# Communication.net
KiCad netlist of a schematic drawn in Altium Designer
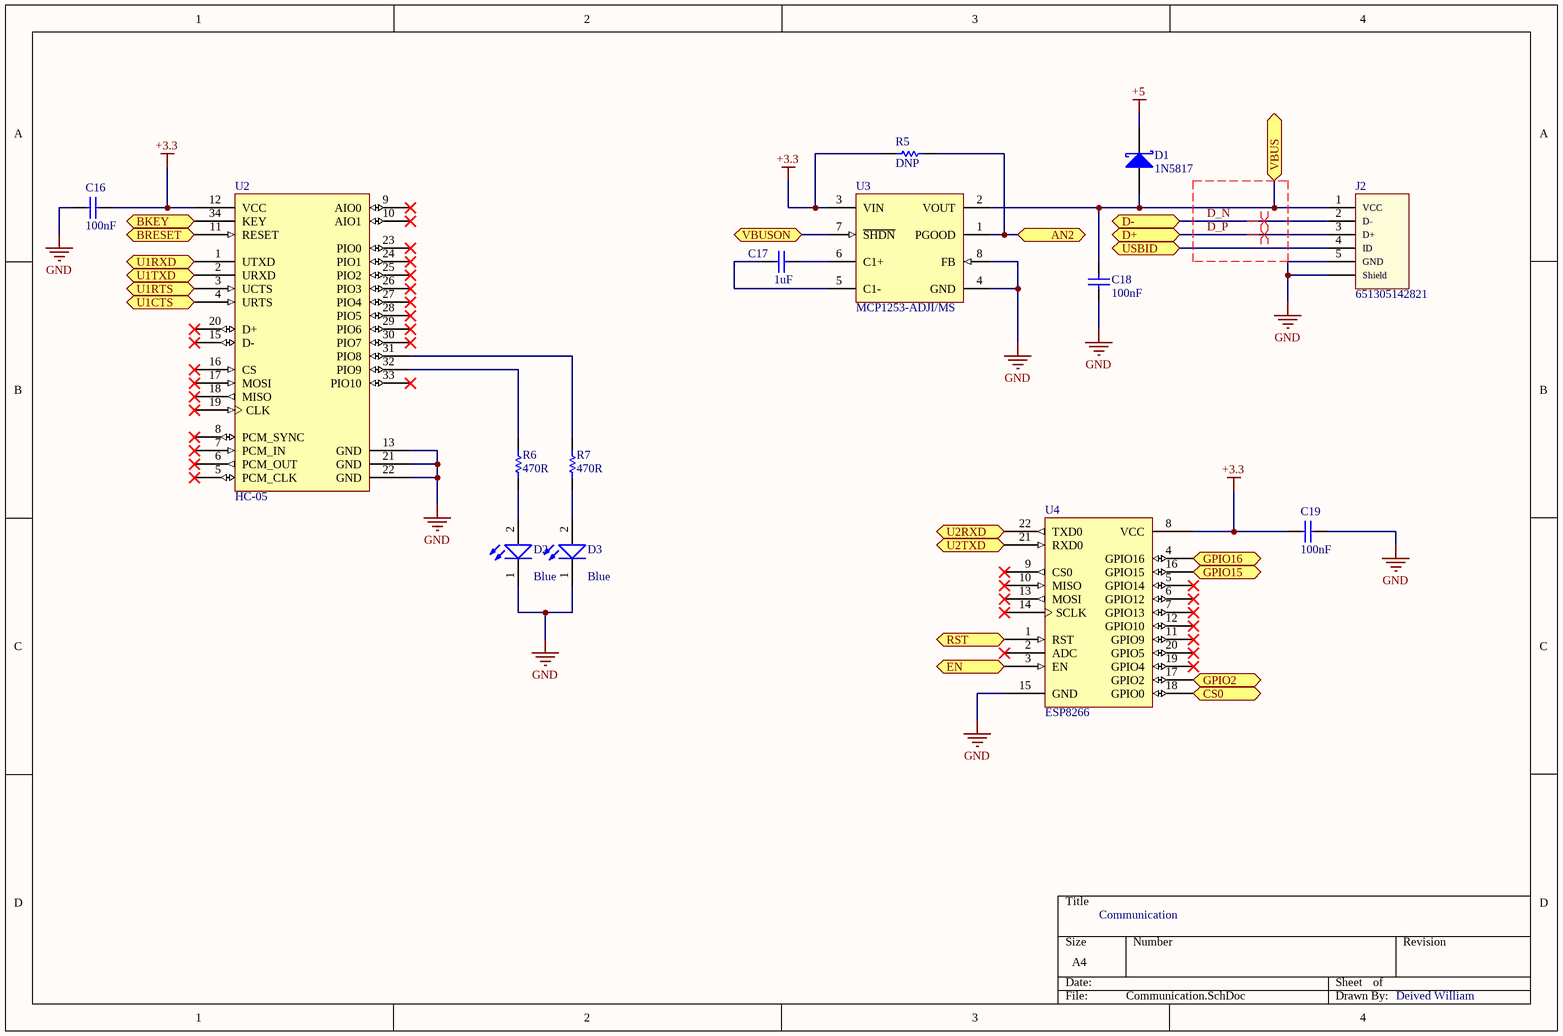
[diagram p0: Communication.SchDoc]

(export (version "E")
  (design (tool "Eeschema 10.0.6"))
  (components
    (comp (ref "C16")
      (value "100nF")
      (footprint "WCAP-CSGP_0603, 1.6x0.8x0.8mm_Reflow")
      (description "WCAP-CSGP Ceramic Capacitors, size 0603, 1.6x0.8x0.8mm, 10V, X7R, 100nF")
      (fields (field (name "PART NUMBER") "885012206020") (field (name "PUBLISHER") "Wurth Elektronik"))
      (libsource (lib "Altium_WCAP-CSGP (rev17a)") (part "885012206020"))
    )
    (comp (ref "C17")
      (value "1uF")
      (footprint "WCAP-CSGP_0603, 1.6x0.8x0.8mm_Reflow")
      (description "WCAP-CSGP Ceramic Capacitors, size 0603, 1.6x0.8x0.8mm, 25V, X5R, 1uF")
      (fields (field (name "PART NUMBER") "885012106022") (field (name "PUBLISHER") "Wurth Elektronik"))
      (libsource (lib "Altium_WCAP-CSGP (rev17a)") (part "885012106022"))
    )
    (comp (ref "C18")
      (value "100nF")
      (footprint "WCAP-CSGP_0603, 1.6x0.8x0.8mm_Reflow")
      (description "WCAP-CSGP Ceramic Capacitors, size 0603, 1.6x0.8x0.8mm, 10V, X7R, 100nF")
      (fields (field (name "PART NUMBER") "885012206020") (field (name "PUBLISHER") "Wurth Elektronik"))
      (libsource (lib "Altium_WCAP-CSGP (rev17a)") (part "885012206020"))
    )
    (comp (ref "C19")
      (value "100nF")
      (footprint "WCAP-CSGP_0603, 1.6x0.8x0.8mm_Reflow")
      (description "WCAP-CSGP Ceramic Capacitors, size 0603, 1.6x0.8x0.8mm, 10V, X7R, 100nF")
      (fields (field (name "PART NUMBER") "885012206020") (field (name "PUBLISHER") "Wurth Elektronik"))
      (libsource (lib "Altium_WCAP-CSGP (rev17a)") (part "885012206020"))
    )
    (comp (ref "D1")
      (value "1N5817")
      (footprint "MELFDIODE")
      (description "Schottky diode Barrier Rectifier")
      (libsource (lib "Componentes Deived Projetos") (part "1N5817"))
    )
    (comp (ref "D2")
      (value "150080BS75000")
      (footprint "WL-SMCW_0805")
      (description "WL-SMCW SMD Mono-color Chip LED Waterclear, size 0805, Blue")
      (fields (field (name "EMITTING COLOR") "Blue") (field (name "PUBLISHER") "Wurth Elektronik"))
      (libsource (lib "ALTIUM-WL-SMCW-rev17a") (part "150080BS75000"))
    )
    (comp (ref "D3")
      (value "150080BS75000")
      (footprint "WL-SMCW_0805")
      (description "WL-SMCW SMD Mono-color Chip LED Waterclear, size 0805, Blue")
      (fields (field (name "EMITTING COLOR") "Blue") (field (name "PUBLISHER") "Wurth Elektronik"))
      (libsource (lib "ALTIUM-WL-SMCW-rev17a") (part "150080BS75000"))
    )
    (comp (ref "J2")
      (value "651305142821")
      (footprint "651305142821")
      (description "Mini USB 2.0 Type AB SMT Horizontal 5 Contacts WR-COM")
      (fields (field (name "PUBLISHER") "Wurth Elektronik"))
      (libsource (lib "Altium_WR-COM (rev17a)") (part "651305142821"))
    )
    (comp (ref "R5")
      (value "DNP")
      (footprint "3-0603")
      (fields (field (name "PUBLISHER") "Altium Limited"))
      (libsource (lib "Panasonic Resistor") (part "ERJ3RB"))
    )
    (comp (ref "R6")
      (value "470R")
      (footprint "3-0603")
      (fields (field (name "PUBLISHER") "Altium Limited"))
      (libsource (lib "Panasonic Resistor") (part "ERJ3RE"))
    )
    (comp (ref "R7")
      (value "470R")
      (footprint "3-0603")
      (fields (field (name "PUBLISHER") "Altium Limited"))
      (libsource (lib "Panasonic Resistor") (part "ERJ3RE"))
    )
    (comp (ref "U2")
      (value "HC-05")
      (footprint "LCC42")
      (description "Modulo Bluetooth HC-05")
      (libsource (lib "Componentes Deived Projetos") (part "Bluetooth HC-05"))
    )
    (comp (ref "U3")
      (value "MCP1253-ADJI/MS")
      (footprint "MSOP-MS8_N")
      (fields (field (name "PUBLISHER") "Altium Limited"))
      (libsource (lib "Microchip Power Mgt Charge Pump") (part "MCP1253-ADJI/MS"))
    )
    (comp (ref "U4")
      (value "ESP8266")
      (footprint "LCC28")
      (description "Modulo WIFI ESP8266")
      (libsource (lib "Componentes Deived Projetos") (part "ESP8266"))
    )
  )
  (nets
    (net (code "1") (name "+3.3") (class "Default")
      (node (ref "C16") (pin "2") (pinfunction "2_2") (pintype "passive"))
      (node (ref "C19") (pin "1") (pinfunction "1_1") (pintype "passive"))
      (node (ref "R5") (pin "1") (pinfunction "1_1") (pintype "passive"))
      (node (ref "U2") (pin "12") (pinfunction "VCC_12") (pintype "power_in"))
      (node (ref "U3") (pin "3") (pinfunction "VIN_3") (pintype "power_in"))
      (node (ref "U4") (pin "8") (pinfunction "VCC_8") (pintype "passive"))
    )
    (net (code "2") (name "+5") (class "Default")
      (node (ref "D1") (pin "2") (pinfunction "K_2") (pintype "passive"))
    )
    (net (code "3") (name "/AN2") (class "Default")
      (node (ref "R5") (pin "2") (pinfunction "2_2") (pintype "passive"))
      (node (ref "U3") (pin "1") (pinfunction "PGOOD_1") (pintype "open_collector"))
    )
    (net (code "4") (name "/BKEY") (class "Default")
      (node (ref "U2") (pin "34") (pinfunction "KEY_34") (pintype "passive"))
    )
    (net (code "5") (name "/BRESET") (class "Default")
      (node (ref "U2") (pin "11") (pinfunction "RESET_11") (pintype "input"))
    )
    (net (code "6") (name "/CS0") (class "Default")
      (node (ref "U4") (pin "18") (pinfunction "GPIO0_18") (pintype "bidirectional"))
    )
    (net (code "7") (name "/D_N") (class "Default")
      (node (ref "J2") (pin "2") (pinfunction "D-_2") (pintype "passive"))
    )
    (net (code "8") (name "/D_P") (class "Default")
      (node (ref "J2") (pin "3") (pinfunction "D+_3") (pintype "passive"))
    )
    (net (code "9") (name "/EN") (class "Default")
      (node (ref "U4") (pin "3") (pinfunction "EN_3") (pintype "input"))
    )
    (net (code "10") (name "/GPIO2") (class "Default")
      (node (ref "U4") (pin "17") (pinfunction "GPIO2_17") (pintype "bidirectional"))
    )
    (net (code "11") (name "/GPIO15") (class "Default")
      (node (ref "U4") (pin "16") (pinfunction "GPIO15_16") (pintype "bidirectional"))
    )
    (net (code "12") (name "/GPIO16") (class "Default")
      (node (ref "U4") (pin "4") (pinfunction "GPIO16_4") (pintype "bidirectional"))
    )
    (net (code "13") (name "/RST") (class "Default")
      (node (ref "U4") (pin "1") (pinfunction "RST_1") (pintype "input"))
    )
    (net (code "14") (name "/U1CTS") (class "Default")
      (node (ref "U2") (pin "4") (pinfunction "URTS_4") (pintype "input"))
    )
    (net (code "15") (name "/U1RTS") (class "Default")
      (node (ref "U2") (pin "3") (pinfunction "UCTS_3") (pintype "input"))
    )
    (net (code "16") (name "/U1RXD") (class "Default")
      (node (ref "U2") (pin "1") (pinfunction "UTXD_1") (pintype "passive"))
    )
    (net (code "17") (name "/U1TXD") (class "Default")
      (node (ref "U2") (pin "2") (pinfunction "URXD_2") (pintype "passive"))
    )
    (net (code "18") (name "/U2RXD") (class "Default")
      (node (ref "U4") (pin "22") (pinfunction "TXD0_22") (pintype "output"))
    )
    (net (code "19") (name "/U2TXD") (class "Default")
      (node (ref "U4") (pin "21") (pinfunction "RXD0_21") (pintype "input"))
    )
    (net (code "20") (name "/USBID") (class "Default")
      (node (ref "J2") (pin "4") (pinfunction "ID_4") (pintype "passive"))
    )
    (net (code "21") (name "/VBUS") (class "Default")
      (node (ref "C18") (pin "2") (pinfunction "2_2") (pintype "passive"))
      (node (ref "D1") (pin "1") (pinfunction "A_1") (pintype "passive"))
      (node (ref "J2") (pin "1") (pinfunction "VCC_1") (pintype "passive"))
      (node (ref "U3") (pin "2") (pinfunction "VOUT_2") (pintype "power_in"))
    )
    (net (code "22") (name "/VBUSON") (class "Default")
      (node (ref "U3") (pin "7") (pinfunction "~{SHDN}_7") (pintype "input"))
    )
    (net (code "23") (name "GND") (class "Default")
      (node (ref "C16") (pin "1") (pinfunction "1_1") (pintype "passive"))
      (node (ref "C18") (pin "1") (pinfunction "1_1") (pintype "passive"))
      (node (ref "C19") (pin "2") (pinfunction "2_2") (pintype "passive"))
      (node (ref "D2") (pin "1") (pinfunction "K_1") (pintype "passive"))
      (node (ref "D3") (pin "1") (pinfunction "K_1") (pintype "passive"))
      (node (ref "J2") (pin "5") (pinfunction "GND_5") (pintype "passive"))
      (node (ref "J2") (pin "Shell") (pinfunction "Shield_Shell") (pintype "passive"))
      (node (ref "U2") (pin "13") (pinfunction "GND_13") (pintype "passive"))
      (node (ref "U2") (pin "21") (pinfunction "GND_21") (pintype "passive"))
      (node (ref "U2") (pin "22") (pinfunction "GND_22") (pintype "passive"))
      (node (ref "U3") (pin "4") (pinfunction "GND_4") (pintype "power_in"))
      (node (ref "U3") (pin "8") (pinfunction "FB_8") (pintype "input"))
      (node (ref "U4") (pin "15") (pinfunction "GND_15") (pintype "passive"))
    )
    (net (code "24") (name "Net-(D2-A)") (class "Default")
      (node (ref "D2") (pin "2") (pinfunction "A_2") (pintype "passive"))
      (node (ref "R6") (pin "1") (pinfunction "1_1") (pintype "passive"))
    )
    (net (code "25") (name "Net-(D3-A)") (class "Default")
      (node (ref "D3") (pin "2") (pinfunction "A_2") (pintype "passive"))
      (node (ref "R7") (pin "1") (pinfunction "1_1") (pintype "passive"))
    )
    (net (code "26") (name "Net-(U2-PIO8)") (class "Default")
      (node (ref "R7") (pin "2") (pinfunction "2_2") (pintype "passive"))
      (node (ref "U2") (pin "31") (pinfunction "PIO8_31") (pintype "bidirectional"))
    )
    (net (code "27") (name "Net-(U2-PIO9)") (class "Default")
      (node (ref "R6") (pin "2") (pinfunction "2_2") (pintype "passive"))
      (node (ref "U2") (pin "32") (pinfunction "PIO9_32") (pintype "bidirectional"))
    )
    (net (code "28") (name "Net-(U3-C1+)") (class "Default")
      (node (ref "C17") (pin "1") (pinfunction "1_1") (pintype "passive"))
      (node (ref "U3") (pin "6") (pinfunction "C1+_6") (pintype "passive"))
    )
    (net (code "29") (name "Net-(U3-C1-)") (class "Default")
      (node (ref "C17") (pin "2") (pinfunction "2_2") (pintype "passive"))
      (node (ref "U3") (pin "5") (pinfunction "C1-_5") (pintype "passive"))
    )
    (net (code "30") (name "unconnected-(U2-AIO0-Pad9)") (class "Default")
      (node (ref "U2") (pin "9") (pinfunction "AIO0_9") (pintype "bidirectional+no_connect"))
    )
    (net (code "31") (name "unconnected-(U2-AIO1-Pad10)") (class "Default")
      (node (ref "U2") (pin "10") (pinfunction "AIO1_10") (pintype "bidirectional+no_connect"))
    )
    (net (code "32") (name "unconnected-(U2-CLK-Pad19)") (class "Default")
      (node (ref "U2") (pin "19") (pinfunction "CLK_19") (pintype "input+no_connect"))
    )
    (net (code "33") (name "unconnected-(U2-CS-Pad16)") (class "Default")
      (node (ref "U2") (pin "16") (pinfunction "CS_16") (pintype "input+no_connect"))
    )
    (net (code "34") (name "unconnected-(U2-D+-Pad20)") (class "Default")
      (node (ref "U2") (pin "20") (pinfunction "D+_20") (pintype "bidirectional+no_connect"))
    )
    (net (code "35") (name "unconnected-(U2-D--Pad15)") (class "Default")
      (node (ref "U2") (pin "15") (pinfunction "D-_15") (pintype "bidirectional+no_connect"))
    )
    (net (code "36") (name "unconnected-(U2-MISO-Pad18)") (class "Default")
      (node (ref "U2") (pin "18") (pinfunction "MISO_18") (pintype "output+no_connect"))
    )
    (net (code "37") (name "unconnected-(U2-MOSI-Pad17)") (class "Default")
      (node (ref "U2") (pin "17") (pinfunction "MOSI_17") (pintype "input+no_connect"))
    )
    (net (code "38") (name "unconnected-(U2-PCM_CLK-Pad5)") (class "Default")
      (node (ref "U2") (pin "5") (pinfunction "PCM_CLK_5") (pintype "bidirectional+no_connect"))
    )
    (net (code "39") (name "unconnected-(U2-PCM_IN-Pad7)") (class "Default")
      (node (ref "U2") (pin "7") (pinfunction "PCM_IN_7") (pintype "input+no_connect"))
    )
    (net (code "40") (name "unconnected-(U2-PCM_OUT-Pad6)") (class "Default")
      (node (ref "U2") (pin "6") (pinfunction "PCM_OUT_6") (pintype "output+no_connect"))
    )
    (net (code "41") (name "unconnected-(U2-PCM_SYNC-Pad8)") (class "Default")
      (node (ref "U2") (pin "8") (pinfunction "PCM_SYNC_8") (pintype "bidirectional+no_connect"))
    )
    (net (code "42") (name "unconnected-(U2-PIO0-Pad23)") (class "Default")
      (node (ref "U2") (pin "23") (pinfunction "PIO0_23") (pintype "bidirectional+no_connect"))
    )
    (net (code "43") (name "unconnected-(U2-PIO1-Pad24)") (class "Default")
      (node (ref "U2") (pin "24") (pinfunction "PIO1_24") (pintype "bidirectional+no_connect"))
    )
    (net (code "44") (name "unconnected-(U2-PIO2-Pad25)") (class "Default")
      (node (ref "U2") (pin "25") (pinfunction "PIO2_25") (pintype "bidirectional+no_connect"))
    )
    (net (code "45") (name "unconnected-(U2-PIO3-Pad26)") (class "Default")
      (node (ref "U2") (pin "26") (pinfunction "PIO3_26") (pintype "bidirectional+no_connect"))
    )
    (net (code "46") (name "unconnected-(U2-PIO4-Pad27)") (class "Default")
      (node (ref "U2") (pin "27") (pinfunction "PIO4_27") (pintype "bidirectional+no_connect"))
    )
    (net (code "47") (name "unconnected-(U2-PIO5-Pad28)") (class "Default")
      (node (ref "U2") (pin "28") (pinfunction "PIO5_28") (pintype "bidirectional+no_connect"))
    )
    (net (code "48") (name "unconnected-(U2-PIO6-Pad29)") (class "Default")
      (node (ref "U2") (pin "29") (pinfunction "PIO6_29") (pintype "bidirectional+no_connect"))
    )
    (net (code "49") (name "unconnected-(U2-PIO7-Pad30)") (class "Default")
      (node (ref "U2") (pin "30") (pinfunction "PIO7_30") (pintype "bidirectional+no_connect"))
    )
    (net (code "50") (name "unconnected-(U2-PIO10-Pad33)") (class "Default")
      (node (ref "U2") (pin "33") (pinfunction "PIO10_33") (pintype "bidirectional+no_connect"))
    )
    (net (code "51") (name "unconnected-(U4-ADC-Pad2)") (class "Default")
      (node (ref "U4") (pin "2") (pinfunction "ADC_2") (pintype "passive+no_connect"))
    )
    (net (code "52") (name "unconnected-(U4-CS0-Pad9)") (class "Default")
      (node (ref "U4") (pin "9") (pinfunction "CS0_9") (pintype "output+no_connect"))
    )
    (net (code "53") (name "unconnected-(U4-GPIO4-Pad19)") (class "Default")
      (node (ref "U4") (pin "19") (pinfunction "GPIO4_19") (pintype "bidirectional+no_connect"))
    )
    (net (code "54") (name "unconnected-(U4-GPIO5-Pad20)") (class "Default")
      (node (ref "U4") (pin "20") (pinfunction "GPIO5_20") (pintype "bidirectional+no_connect"))
    )
    (net (code "55") (name "unconnected-(U4-GPIO9-Pad11)") (class "Default")
      (node (ref "U4") (pin "11") (pinfunction "GPIO9_11") (pintype "bidirectional+no_connect"))
    )
    (net (code "56") (name "unconnected-(U4-GPIO10-Pad12)") (class "Default")
      (node (ref "U4") (pin "12") (pinfunction "GPIO10_12") (pintype "bidirectional+no_connect"))
    )
    (net (code "57") (name "unconnected-(U4-GPIO12-Pad6)") (class "Default")
      (node (ref "U4") (pin "6") (pinfunction "GPIO12_6") (pintype "bidirectional+no_connect"))
    )
    (net (code "58") (name "unconnected-(U4-GPIO13-Pad7)") (class "Default")
      (node (ref "U4") (pin "7") (pinfunction "GPIO13_7") (pintype "bidirectional+no_connect"))
    )
    (net (code "59") (name "unconnected-(U4-GPIO14-Pad5)") (class "Default")
      (node (ref "U4") (pin "5") (pinfunction "GPIO14_5") (pintype "bidirectional+no_connect"))
    )
    (net (code "60") (name "unconnected-(U4-MISO-Pad10)") (class "Default")
      (node (ref "U4") (pin "10") (pinfunction "MISO_10") (pintype "input+no_connect"))
    )
    (net (code "61") (name "unconnected-(U4-MOSI-Pad13)") (class "Default")
      (node (ref "U4") (pin "13") (pinfunction "MOSI_13") (pintype "output+no_connect"))
    )
    (net (code "62") (name "unconnected-(U4-SCLK-Pad14)") (class "Default")
      (node (ref "U4") (pin "14") (pinfunction "SCLK_14") (pintype "passive+no_connect"))
    )
  )
)
